# rcsdcard_v1.net
KiCad netlist of a schematic drawn in EAGLE
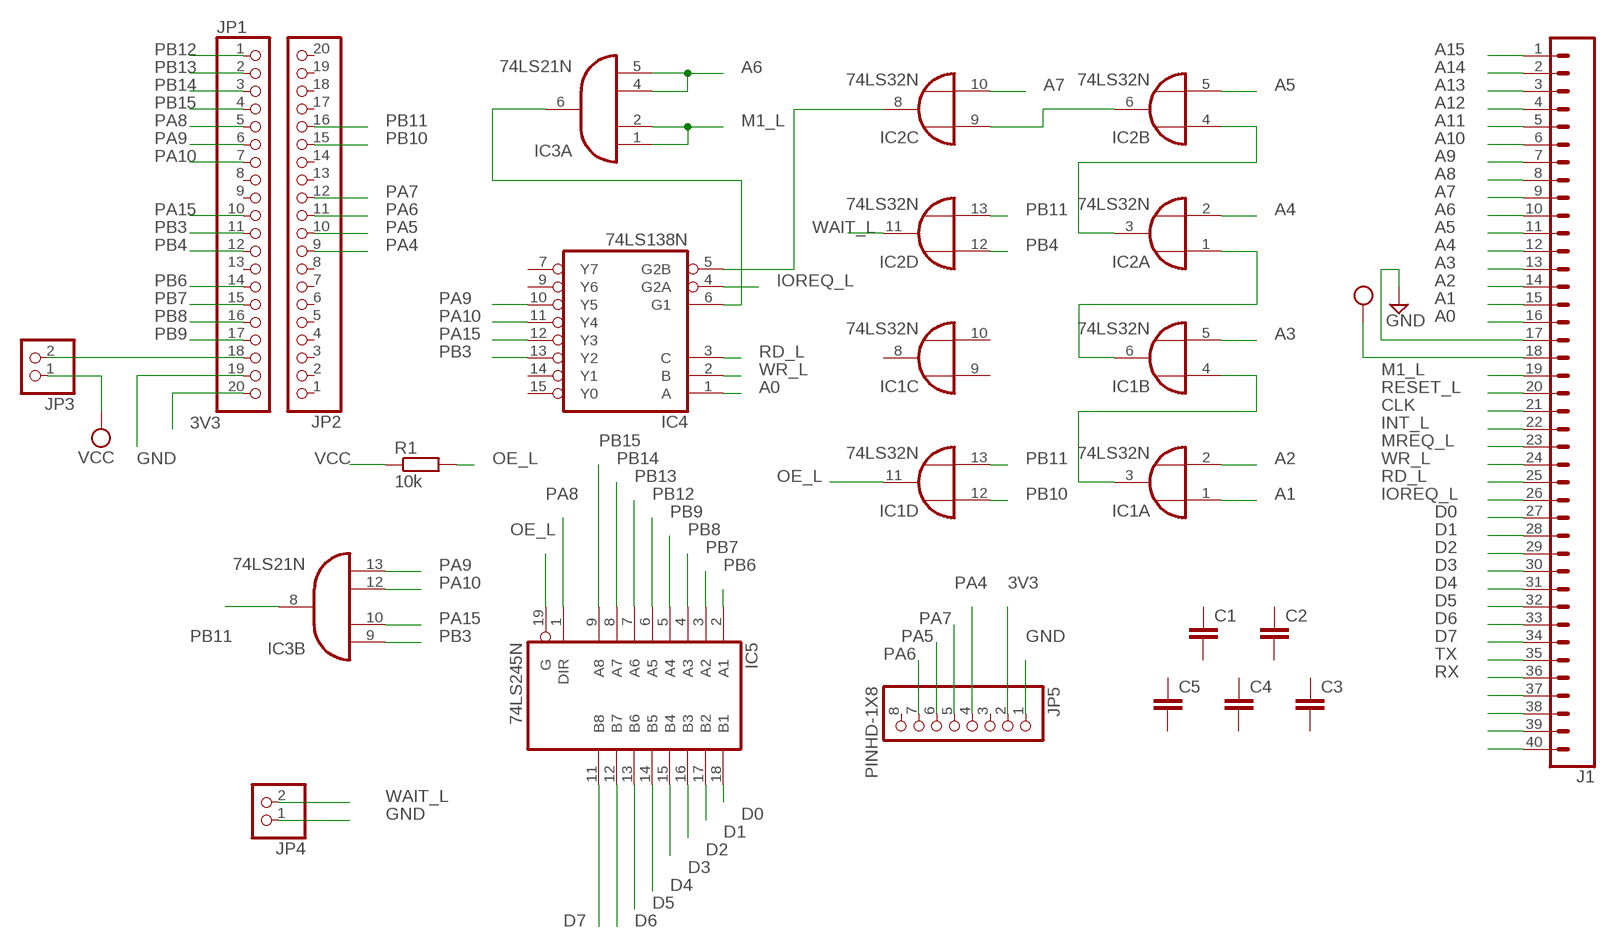
[diagram p0: schematic, sheet 1]

(export (version "E")
  (design (tool "Eeschema 10.0.6"))
  (components
    (comp (ref "C1")
      (value "C-EU050-025X075")
      (footprint "eagle-import:C050-025X075")
      (libsource (lib "eagle-import") (part "C-EU050-025X075"))
    )
    (comp (ref "C2")
      (value "C-EU050-025X075")
      (footprint "eagle-import:C050-025X075")
      (libsource (lib "eagle-import") (part "C-EU050-025X075"))
    )
    (comp (ref "C3")
      (value "C-EU050-025X075")
      (footprint "eagle-import:C050-025X075")
      (libsource (lib "eagle-import") (part "C-EU050-025X075"))
    )
    (comp (ref "C4")
      (value "C-EU050-025X075")
      (footprint "eagle-import:C050-025X075")
      (libsource (lib "eagle-import") (part "C-EU050-025X075"))
    )
    (comp (ref "C5")
      (value "C-EU050-025X075")
      (footprint "eagle-import:C050-025X075")
      (libsource (lib "eagle-import") (part "C-EU050-025X075"))
    )
    (comp (ref "IC1")
      (value "74LS32N")
      (footprint "eagle-import:DIL14")
      (libsource (lib "eagle-import") (part "7432NLS"))
    )
    (comp (ref "IC2")
      (value "74LS32N")
      (footprint "eagle-import:DIL14")
      (libsource (lib "eagle-import") (part "7432NLS"))
    )
    (comp (ref "IC3")
      (value "74LS21N")
      (footprint "eagle-import:DIL14")
      (libsource (lib "eagle-import") (part "7421NLS"))
    )
    (comp (ref "IC4")
      (value "74LS138N")
      (footprint "eagle-import:DIL16")
      (libsource (lib "eagle-import") (part "74138NLS"))
    )
    (comp (ref "IC5")
      (value "74LS245N")
      (footprint "eagle-import:DIL20")
      (libsource (lib "eagle-import") (part "74245NLS"))
    )
    (comp (ref "J1")
      (value "CONN_40OFFSET")
      (footprint "eagle-import:1X40_OFFSET")
      (libsource (lib "eagle-import") (part "CONN_40OFFSET"))
    )
    (comp (ref "JP1")
      (value "PINHD-1X20")
      (footprint "eagle-import:1X20")
      (libsource (lib "eagle-import") (part "PINHD-1X20"))
    )
    (comp (ref "JP2")
      (value "PINHD-1X20")
      (footprint "eagle-import:1X20")
      (libsource (lib "eagle-import") (part "PINHD-1X20"))
    )
    (comp (ref "JP3")
      (value "PINHD-1X2")
      (footprint "eagle-import:1X02")
      (libsource (lib "eagle-import") (part "PINHD-1X2"))
    )
    (comp (ref "JP4")
      (value "PINHD-1X2")
      (footprint "eagle-import:1X02")
      (libsource (lib "eagle-import") (part "PINHD-1X2"))
    )
    (comp (ref "JP5")
      (value "PINHD-1X8")
      (footprint "eagle-import:1X08")
      (libsource (lib "eagle-import") (part "PINHD-1X8"))
    )
    (comp (ref "R1")
      (value "10k")
      (footprint "eagle-import:0204_7")
      (libsource (lib "eagle-import") (part "R-EU_0204/7"))
    )
  )
  (nets
    (net (code "1") (name "/3V3") (class "Default")
      (node (ref "JP1") (pin "20") (pinfunction "20_20") (pintype "passive"))
      (node (ref "JP5") (pin "2") (pinfunction "2_2") (pintype "passive"))
    )
    (net (code "2") (name "/A0") (class "Default")
      (node (ref "IC4") (pin "1") (pinfunction "A_1") (pintype "input"))
      (node (ref "J1") (pin "16") (pinfunction "16_16") (pintype "passive"))
    )
    (net (code "3") (name "/A1") (class "Default")
      (node (ref "IC1") (pin "1") (pinfunction "I0_1") (pintype "input"))
      (node (ref "J1") (pin "15") (pinfunction "15_15") (pintype "passive"))
    )
    (net (code "4") (name "/A2") (class "Default")
      (node (ref "IC1") (pin "2") (pinfunction "I1_2") (pintype "input"))
      (node (ref "J1") (pin "14") (pinfunction "14_14") (pintype "passive"))
    )
    (net (code "5") (name "/A3") (class "Default")
      (node (ref "IC1") (pin "5") (pinfunction "I1_5") (pintype "input"))
      (node (ref "J1") (pin "13") (pinfunction "13_13") (pintype "passive"))
    )
    (net (code "6") (name "/A4") (class "Default")
      (node (ref "IC2") (pin "2") (pinfunction "I1_2") (pintype "input"))
      (node (ref "J1") (pin "12") (pinfunction "12_12") (pintype "passive"))
    )
    (net (code "7") (name "/A5") (class "Default")
      (node (ref "IC1") (pin "6") (pinfunction "O_6") (pintype "output"))
      (node (ref "IC2") (pin "1") (pinfunction "I0_1") (pintype "input"))
      (node (ref "IC2") (pin "5") (pinfunction "I1_5") (pintype "input"))
      (node (ref "J1") (pin "11") (pinfunction "11_11") (pintype "passive"))
    )
    (net (code "8") (name "/A6") (class "Default")
      (node (ref "IC3") (pin "4") (pinfunction "I2_4") (pintype "input"))
      (node (ref "IC3") (pin "5") (pinfunction "I3_5") (pintype "input"))
      (node (ref "J1") (pin "10") (pinfunction "10_10") (pintype "passive"))
    )
    (net (code "9") (name "/A7") (class "Default")
      (node (ref "IC2") (pin "10") (pinfunction "I1_10") (pintype "input"))
      (node (ref "J1") (pin "9") (pinfunction "9_9") (pintype "passive"))
    )
    (net (code "10") (name "/A8") (class "Default")
      (node (ref "J1") (pin "8") (pinfunction "8_8") (pintype "passive"))
    )
    (net (code "11") (name "/A9") (class "Default")
      (node (ref "J1") (pin "7") (pinfunction "7_7") (pintype "passive"))
    )
    (net (code "12") (name "/A10") (class "Default")
      (node (ref "J1") (pin "6") (pinfunction "6_6") (pintype "passive"))
    )
    (net (code "13") (name "/A11") (class "Default")
      (node (ref "J1") (pin "5") (pinfunction "5_5") (pintype "passive"))
    )
    (net (code "14") (name "/A12") (class "Default")
      (node (ref "J1") (pin "4") (pinfunction "4_4") (pintype "passive"))
    )
    (net (code "15") (name "/A13") (class "Default")
      (node (ref "J1") (pin "3") (pinfunction "3_3") (pintype "passive"))
    )
    (net (code "16") (name "/A14") (class "Default")
      (node (ref "J1") (pin "2") (pinfunction "2_2") (pintype "passive"))
    )
    (net (code "17") (name "/A15") (class "Default")
      (node (ref "J1") (pin "1") (pinfunction "1_1") (pintype "passive"))
    )
    (net (code "18") (name "/CLK") (class "Default")
      (node (ref "J1") (pin "21") (pinfunction "21_21") (pintype "passive"))
    )
    (net (code "19") (name "/D0") (class "Default")
      (node (ref "IC5") (pin "18") (pinfunction "B1_18") (pintype "bidirectional"))
      (node (ref "J1") (pin "27") (pinfunction "27_27") (pintype "passive"))
    )
    (net (code "20") (name "/D1") (class "Default")
      (node (ref "IC5") (pin "17") (pinfunction "B2_17") (pintype "bidirectional"))
      (node (ref "J1") (pin "28") (pinfunction "28_28") (pintype "passive"))
    )
    (net (code "21") (name "/D2") (class "Default")
      (node (ref "IC5") (pin "16") (pinfunction "B3_16") (pintype "bidirectional"))
      (node (ref "J1") (pin "29") (pinfunction "29_29") (pintype "passive"))
    )
    (net (code "22") (name "/D3") (class "Default")
      (node (ref "IC5") (pin "15") (pinfunction "B4_15") (pintype "bidirectional"))
      (node (ref "J1") (pin "30") (pinfunction "30_30") (pintype "passive"))
    )
    (net (code "23") (name "/D4") (class "Default")
      (node (ref "IC5") (pin "14") (pinfunction "B5_14") (pintype "bidirectional"))
      (node (ref "J1") (pin "31") (pinfunction "31_31") (pintype "passive"))
    )
    (net (code "24") (name "/D5") (class "Default")
      (node (ref "IC5") (pin "13") (pinfunction "B6_13") (pintype "bidirectional"))
      (node (ref "J1") (pin "32") (pinfunction "32_32") (pintype "passive"))
    )
    (net (code "25") (name "/D6") (class "Default")
      (node (ref "IC5") (pin "12") (pinfunction "B7_12") (pintype "bidirectional"))
      (node (ref "J1") (pin "33") (pinfunction "33_33") (pintype "passive"))
    )
    (net (code "26") (name "/D7") (class "Default")
      (node (ref "IC5") (pin "11") (pinfunction "B8_11") (pintype "bidirectional"))
      (node (ref "J1") (pin "34") (pinfunction "34_34") (pintype "passive"))
    )
    (net (code "27") (name "/INT_L") (class "Default")
      (node (ref "J1") (pin "22") (pinfunction "22_22") (pintype "passive"))
    )
    (net (code "28") (name "/IOREQ_L") (class "Default")
      (node (ref "IC4") (pin "4") (pinfunction "G2A_4") (pintype "input"))
      (node (ref "J1") (pin "26") (pinfunction "26_26") (pintype "passive"))
    )
    (net (code "29") (name "/M1_L") (class "Default")
      (node (ref "IC3") (pin "1") (pinfunction "I0_1") (pintype "input"))
      (node (ref "IC3") (pin "2") (pinfunction "I1_2") (pintype "input"))
      (node (ref "J1") (pin "19") (pinfunction "19_19") (pintype "passive"))
    )
    (net (code "30") (name "/MREQ_L") (class "Default")
      (node (ref "J1") (pin "23") (pinfunction "23_23") (pintype "passive"))
    )
    (net (code "31") (name "/OE_L") (class "Default")
      (node (ref "IC1") (pin "11") (pinfunction "O_11") (pintype "output"))
      (node (ref "IC5") (pin "19") (pinfunction "G_19") (pintype "input"))
      (node (ref "R1") (pin "2") (pinfunction "2_2") (pintype "passive"))
    )
    (net (code "32") (name "/PA4") (class "Default")
      (node (ref "JP2") (pin "9") (pinfunction "9_9") (pintype "passive"))
      (node (ref "JP5") (pin "4") (pinfunction "4_4") (pintype "passive"))
    )
    (net (code "33") (name "/PA5") (class "Default")
      (node (ref "JP2") (pin "10") (pinfunction "10_10") (pintype "passive"))
      (node (ref "JP5") (pin "6") (pinfunction "6_6") (pintype "passive"))
    )
    (net (code "34") (name "/PA6") (class "Default")
      (node (ref "JP2") (pin "11") (pinfunction "11_11") (pintype "passive"))
      (node (ref "JP5") (pin "7") (pinfunction "7_7") (pintype "passive"))
    )
    (net (code "35") (name "/PA7") (class "Default")
      (node (ref "JP2") (pin "12") (pinfunction "12_12") (pintype "passive"))
      (node (ref "JP5") (pin "5") (pinfunction "5_5") (pintype "passive"))
    )
    (net (code "36") (name "/PA8") (class "Default")
      (node (ref "IC5") (pin "1") (pinfunction "DIR_1") (pintype "input"))
      (node (ref "JP1") (pin "5") (pinfunction "5_5") (pintype "passive"))
    )
    (net (code "37") (name "/PA9") (class "Default")
      (node (ref "IC3") (pin "13") (pinfunction "I3_13") (pintype "input"))
      (node (ref "IC4") (pin "10") (pinfunction "Y5_10") (pintype "output"))
      (node (ref "JP1") (pin "6") (pinfunction "6_6") (pintype "passive"))
    )
    (net (code "38") (name "/PA10") (class "Default")
      (node (ref "IC3") (pin "12") (pinfunction "I2_12") (pintype "input"))
      (node (ref "IC4") (pin "11") (pinfunction "Y4_11") (pintype "output"))
      (node (ref "JP1") (pin "7") (pinfunction "7_7") (pintype "passive"))
    )
    (net (code "39") (name "/PA15") (class "Default")
      (node (ref "IC3") (pin "10") (pinfunction "I1_10") (pintype "input"))
      (node (ref "IC4") (pin "12") (pinfunction "Y3_12") (pintype "output"))
      (node (ref "JP1") (pin "10") (pinfunction "10_10") (pintype "passive"))
    )
    (net (code "40") (name "/PB3") (class "Default")
      (node (ref "IC3") (pin "9") (pinfunction "I0_9") (pintype "input"))
      (node (ref "IC4") (pin "13") (pinfunction "Y2_13") (pintype "output"))
      (node (ref "JP1") (pin "11") (pinfunction "11_11") (pintype "passive"))
    )
    (net (code "41") (name "/PB4") (class "Default")
      (node (ref "IC2") (pin "12") (pinfunction "I0_12") (pintype "input"))
      (node (ref "JP1") (pin "12") (pinfunction "12_12") (pintype "passive"))
    )
    (net (code "42") (name "/PB6") (class "Default")
      (node (ref "IC5") (pin "2") (pinfunction "A1_2") (pintype "bidirectional"))
      (node (ref "JP1") (pin "14") (pinfunction "14_14") (pintype "passive"))
    )
    (net (code "43") (name "/PB7") (class "Default")
      (node (ref "IC5") (pin "3") (pinfunction "A2_3") (pintype "bidirectional"))
      (node (ref "JP1") (pin "15") (pinfunction "15_15") (pintype "passive"))
    )
    (net (code "44") (name "/PB8") (class "Default")
      (node (ref "IC5") (pin "4") (pinfunction "A3_4") (pintype "bidirectional"))
      (node (ref "JP1") (pin "16") (pinfunction "16_16") (pintype "passive"))
    )
    (net (code "45") (name "/PB9") (class "Default")
      (node (ref "IC5") (pin "5") (pinfunction "A4_5") (pintype "bidirectional"))
      (node (ref "JP1") (pin "17") (pinfunction "17_17") (pintype "passive"))
    )
    (net (code "46") (name "/PB10") (class "Default")
      (node (ref "IC1") (pin "12") (pinfunction "I0_12") (pintype "input"))
      (node (ref "JP2") (pin "15") (pinfunction "15_15") (pintype "passive"))
    )
    (net (code "47") (name "/PB11") (class "Default")
      (node (ref "IC1") (pin "13") (pinfunction "I1_13") (pintype "input"))
      (node (ref "IC2") (pin "13") (pinfunction "I1_13") (pintype "input"))
      (node (ref "IC3") (pin "8") (pinfunction "O_8") (pintype "output"))
      (node (ref "JP2") (pin "16") (pinfunction "16_16") (pintype "passive"))
    )
    (net (code "48") (name "/PB12") (class "Default")
      (node (ref "IC5") (pin "6") (pinfunction "A5_6") (pintype "bidirectional"))
      (node (ref "JP1") (pin "1") (pinfunction "1_1") (pintype "passive"))
    )
    (net (code "49") (name "/PB13") (class "Default")
      (node (ref "IC5") (pin "7") (pinfunction "A6_7") (pintype "bidirectional"))
      (node (ref "JP1") (pin "2") (pinfunction "2_2") (pintype "passive"))
    )
    (net (code "50") (name "/PB14") (class "Default")
      (node (ref "IC5") (pin "8") (pinfunction "A7_8") (pintype "bidirectional"))
      (node (ref "JP1") (pin "3") (pinfunction "3_3") (pintype "passive"))
    )
    (net (code "51") (name "/PB15") (class "Default")
      (node (ref "IC5") (pin "9") (pinfunction "A8_9") (pintype "bidirectional"))
      (node (ref "JP1") (pin "4") (pinfunction "4_4") (pintype "passive"))
    )
    (net (code "52") (name "/RD_L") (class "Default")
      (node (ref "IC4") (pin "3") (pinfunction "C_3") (pintype "input"))
      (node (ref "J1") (pin "25") (pinfunction "25_25") (pintype "passive"))
    )
    (net (code "53") (name "/RESET_L") (class "Default")
      (node (ref "J1") (pin "20") (pinfunction "20_20") (pintype "passive"))
    )
    (net (code "54") (name "/RX") (class "Default")
      (node (ref "J1") (pin "36") (pinfunction "36_36") (pintype "passive"))
    )
    (net (code "55") (name "/TX") (class "Default")
      (node (ref "J1") (pin "35") (pinfunction "35_35") (pintype "passive"))
    )
    (net (code "56") (name "/WAIT_L") (class "Default")
      (node (ref "IC2") (pin "11") (pinfunction "O_11") (pintype "output"))
      (node (ref "JP4") (pin "2") (pinfunction "2_2") (pintype "passive"))
    )
    (net (code "57") (name "/WR_L") (class "Default")
      (node (ref "IC4") (pin "2") (pinfunction "B_2") (pintype "input"))
      (node (ref "J1") (pin "24") (pinfunction "24_24") (pintype "passive"))
    )
    (net (code "58") (name "GND") (class "Default")
      (node (ref "J1") (pin "17") (pinfunction "17_17") (pintype "passive"))
      (node (ref "JP1") (pin "19") (pinfunction "19_19") (pintype "passive"))
      (node (ref "JP4") (pin "1") (pinfunction "1_1") (pintype "passive"))
      (node (ref "JP5") (pin "1") (pinfunction "1_1") (pintype "passive"))
    )
    (net (code "59") (name "Net-(IC1A-O)") (class "Default")
      (node (ref "IC1") (pin "3") (pinfunction "O_3") (pintype "output"))
      (node (ref "IC1") (pin "4") (pinfunction "I0_4") (pintype "input"))
    )
    (net (code "60") (name "Net-(IC2A-O)") (class "Default")
      (node (ref "IC2") (pin "3") (pinfunction "O_3") (pintype "output"))
      (node (ref "IC2") (pin "4") (pinfunction "I0_4") (pintype "input"))
    )
    (net (code "61") (name "Net-(IC2B-O)") (class "Default")
      (node (ref "IC2") (pin "6") (pinfunction "O_6") (pintype "output"))
      (node (ref "IC2") (pin "9") (pinfunction "I0_9") (pintype "input"))
    )
    (net (code "62") (name "Net-(IC2C-O)") (class "Default")
      (node (ref "IC2") (pin "8") (pinfunction "O_8") (pintype "output"))
      (node (ref "IC4") (pin "5") (pinfunction "G2B_5") (pintype "input"))
    )
    (net (code "63") (name "Net-(IC3A-O)") (class "Default")
      (node (ref "IC3") (pin "6") (pinfunction "O_6") (pintype "output"))
      (node (ref "IC4") (pin "6") (pinfunction "G1_6") (pintype "input"))
    )
    (net (code "64") (name "Net-(JP1-Pad18)") (class "Default")
      (node (ref "JP1") (pin "18") (pinfunction "18_18") (pintype "passive"))
      (node (ref "JP3") (pin "2") (pinfunction "2_2") (pintype "passive"))
    )
    (net (code "65") (name "VCC") (class "Default")
      (node (ref "J1") (pin "18") (pinfunction "18_18") (pintype "passive"))
      (node (ref "JP3") (pin "1") (pinfunction "1_1") (pintype "passive"))
      (node (ref "R1") (pin "1") (pinfunction "1_1") (pintype "passive"))
    )
    (net (code "66") (name "unconnected-(C1-Pad1)") (class "Default")
      (node (ref "C1") (pin "1") (pinfunction "1_1") (pintype "passive"))
    )
    (net (code "67") (name "unconnected-(C1-Pad2)") (class "Default")
      (node (ref "C1") (pin "2") (pinfunction "2_2") (pintype "passive"))
    )
    (net (code "68") (name "unconnected-(C2-Pad1)") (class "Default")
      (node (ref "C2") (pin "1") (pinfunction "1_1") (pintype "passive"))
    )
    (net (code "69") (name "unconnected-(C2-Pad2)") (class "Default")
      (node (ref "C2") (pin "2") (pinfunction "2_2") (pintype "passive"))
    )
    (net (code "70") (name "unconnected-(C3-Pad1)") (class "Default")
      (node (ref "C3") (pin "1") (pinfunction "1_1") (pintype "passive"))
    )
    (net (code "71") (name "unconnected-(C3-Pad2)") (class "Default")
      (node (ref "C3") (pin "2") (pinfunction "2_2") (pintype "passive"))
    )
    (net (code "72") (name "unconnected-(C4-Pad1)") (class "Default")
      (node (ref "C4") (pin "1") (pinfunction "1_1") (pintype "passive"))
    )
    (net (code "73") (name "unconnected-(C4-Pad2)") (class "Default")
      (node (ref "C4") (pin "2") (pinfunction "2_2") (pintype "passive"))
    )
    (net (code "74") (name "unconnected-(C5-Pad1)") (class "Default")
      (node (ref "C5") (pin "1") (pinfunction "1_1") (pintype "passive"))
    )
    (net (code "75") (name "unconnected-(C5-Pad2)") (class "Default")
      (node (ref "C5") (pin "2") (pinfunction "2_2") (pintype "passive"))
    )
    (net (code "76") (name "unconnected-(IC1C-I0-Pad9)") (class "Default")
      (node (ref "IC1") (pin "9") (pinfunction "I0_9") (pintype "input"))
    )
    (net (code "77") (name "unconnected-(IC1C-I1-Pad10)") (class "Default")
      (node (ref "IC1") (pin "10") (pinfunction "I1_10") (pintype "input"))
    )
    (net (code "78") (name "unconnected-(IC1C-O-Pad8)") (class "Default")
      (node (ref "IC1") (pin "8") (pinfunction "O_8") (pintype "output"))
    )
    (net (code "79") (name "unconnected-(IC4A-Y0-Pad15)") (class "Default")
      (node (ref "IC4") (pin "15") (pinfunction "Y0_15") (pintype "output"))
    )
    (net (code "80") (name "unconnected-(IC4A-Y1-Pad14)") (class "Default")
      (node (ref "IC4") (pin "14") (pinfunction "Y1_14") (pintype "output"))
    )
    (net (code "81") (name "unconnected-(IC4A-Y6-Pad9)") (class "Default")
      (node (ref "IC4") (pin "9") (pinfunction "Y6_9") (pintype "output"))
    )
    (net (code "82") (name "unconnected-(IC4A-Y7-Pad7)") (class "Default")
      (node (ref "IC4") (pin "7") (pinfunction "Y7_7") (pintype "output"))
    )
    (net (code "83") (name "unconnected-(J1-Pad37)") (class "Default")
      (node (ref "J1") (pin "37") (pinfunction "37_37") (pintype "passive"))
    )
    (net (code "84") (name "unconnected-(J1-Pad38)") (class "Default")
      (node (ref "J1") (pin "38") (pinfunction "38_38") (pintype "passive"))
    )
    (net (code "85") (name "unconnected-(J1-Pad39)") (class "Default")
      (node (ref "J1") (pin "39") (pinfunction "39_39") (pintype "passive"))
    )
    (net (code "86") (name "unconnected-(J1-Pad40)") (class "Default")
      (node (ref "J1") (pin "40") (pinfunction "40_40") (pintype "passive"))
    )
    (net (code "87") (name "unconnected-(JP1-Pad8)") (class "Default")
      (node (ref "JP1") (pin "8") (pinfunction "8_8") (pintype "passive"))
    )
    (net (code "88") (name "unconnected-(JP1-Pad9)") (class "Default")
      (node (ref "JP1") (pin "9") (pinfunction "9_9") (pintype "passive"))
    )
    (net (code "89") (name "unconnected-(JP1-Pad13)") (class "Default")
      (node (ref "JP1") (pin "13") (pinfunction "13_13") (pintype "passive"))
    )
    (net (code "90") (name "unconnected-(JP2-Pad1)") (class "Default")
      (node (ref "JP2") (pin "1") (pinfunction "1_1") (pintype "passive"))
    )
    (net (code "91") (name "unconnected-(JP2-Pad2)") (class "Default")
      (node (ref "JP2") (pin "2") (pinfunction "2_2") (pintype "passive"))
    )
    (net (code "92") (name "unconnected-(JP2-Pad3)") (class "Default")
      (node (ref "JP2") (pin "3") (pinfunction "3_3") (pintype "passive"))
    )
    (net (code "93") (name "unconnected-(JP2-Pad4)") (class "Default")
      (node (ref "JP2") (pin "4") (pinfunction "4_4") (pintype "passive"))
    )
    (net (code "94") (name "unconnected-(JP2-Pad5)") (class "Default")
      (node (ref "JP2") (pin "5") (pinfunction "5_5") (pintype "passive"))
    )
    (net (code "95") (name "unconnected-(JP2-Pad6)") (class "Default")
      (node (ref "JP2") (pin "6") (pinfunction "6_6") (pintype "passive"))
    )
    (net (code "96") (name "unconnected-(JP2-Pad7)") (class "Default")
      (node (ref "JP2") (pin "7") (pinfunction "7_7") (pintype "passive"))
    )
    (net (code "97") (name "unconnected-(JP2-Pad8)") (class "Default")
      (node (ref "JP2") (pin "8") (pinfunction "8_8") (pintype "passive"))
    )
    (net (code "98") (name "unconnected-(JP2-Pad13)") (class "Default")
      (node (ref "JP2") (pin "13") (pinfunction "13_13") (pintype "passive"))
    )
    (net (code "99") (name "unconnected-(JP2-Pad14)") (class "Default")
      (node (ref "JP2") (pin "14") (pinfunction "14_14") (pintype "passive"))
    )
    (net (code "100") (name "unconnected-(JP2-Pad17)") (class "Default")
      (node (ref "JP2") (pin "17") (pinfunction "17_17") (pintype "passive"))
    )
    (net (code "101") (name "unconnected-(JP2-Pad18)") (class "Default")
      (node (ref "JP2") (pin "18") (pinfunction "18_18") (pintype "passive"))
    )
    (net (code "102") (name "unconnected-(JP2-Pad19)") (class "Default")
      (node (ref "JP2") (pin "19") (pinfunction "19_19") (pintype "passive"))
    )
    (net (code "103") (name "unconnected-(JP2-Pad20)") (class "Default")
      (node (ref "JP2") (pin "20") (pinfunction "20_20") (pintype "passive"))
    )
    (net (code "104") (name "unconnected-(JP5-Pad3)") (class "Default")
      (node (ref "JP5") (pin "3") (pinfunction "3_3") (pintype "passive"))
    )
    (net (code "105") (name "unconnected-(JP5-Pad8)") (class "Default")
      (node (ref "JP5") (pin "8") (pinfunction "8_8") (pintype "passive"))
    )
  )
)
